# Multiplex_Registers.net
KiCad netlist of a schematic drawn in Altium Designer
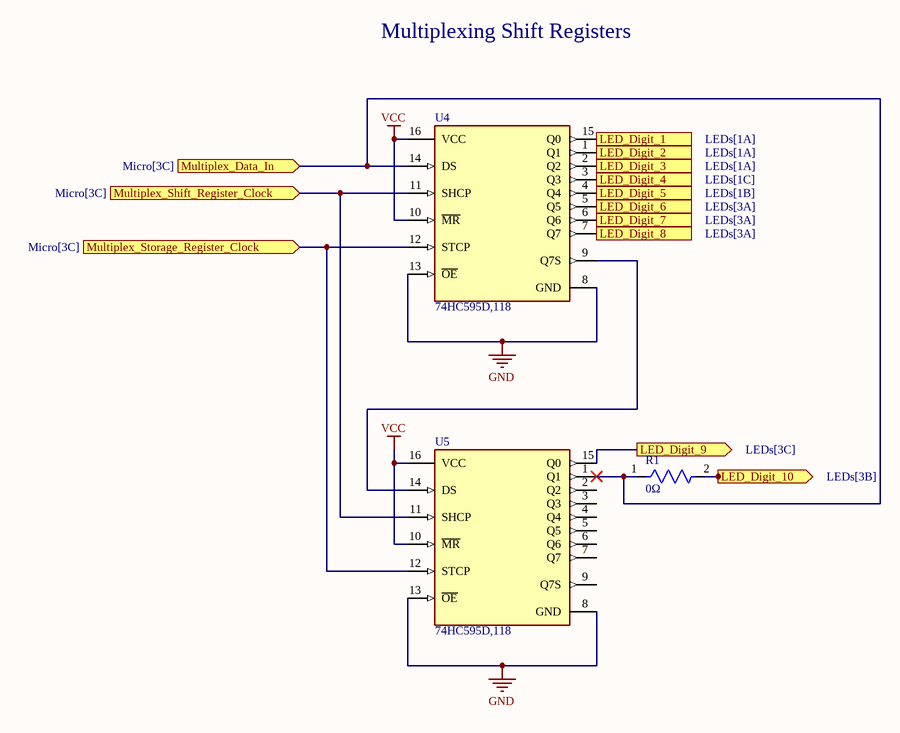
[diagram p0: Multiplex_Registers.SchDoc]

(export (version "E")
  (design (tool "Eeschema 10.0.6"))
  (components
    (comp (ref "R1")
      (value "CRCW04020000Z0ED")
      (footprint "FP-CRCW0402-e3-IPC_C")
      (description "RES Thick Film, 0Ω, 0.063W, 0402")
      (fields (field (name "TOLERANCE") "5%"))
      (libsource (lib "Altium Content Vault") (part "1029c3af85768c4190bb7ad29bc67b5"))
    )
    (comp (ref "U4")
      (value "74HC595D,118")
      (footprint "FP-SOT109-1-IPC_C")
      (description "IC SHIFT REGISTER 8BIT 16SOIC")
      (libsource (lib "Altium Content Vault") (part "7b153f231cfcc3ac06dee253bd56617"))
    )
    (comp (ref "U5")
      (value "74HC595D,118")
      (footprint "FP-SOT109-1-IPC_C")
      (description "IC SHIFT REGISTER 8BIT 16SOIC")
      (libsource (lib "Altium Content Vault") (part "7b153f231cfcc3ac06dee253bd56617"))
    )
  )
  (nets
    (net (code "1") (name "/LED_Digit_1") (class "Default")
      (node (ref "U4") (pin "15") (pinfunction "Q0_15") (pintype "output"))
    )
    (net (code "2") (name "/LED_Digit_2") (class "Default")
      (node (ref "U4") (pin "1") (pinfunction "Q1_1") (pintype "output"))
    )
    (net (code "3") (name "/LED_Digit_3") (class "Default")
      (node (ref "U4") (pin "2") (pinfunction "Q2_2") (pintype "output"))
    )
    (net (code "4") (name "/LED_Digit_4") (class "Default")
      (node (ref "U4") (pin "3") (pinfunction "Q3_3") (pintype "output"))
    )
    (net (code "5") (name "/LED_Digit_5") (class "Default")
      (node (ref "U4") (pin "4") (pinfunction "Q4_4") (pintype "output"))
    )
    (net (code "6") (name "/LED_Digit_6") (class "Default")
      (node (ref "U4") (pin "5") (pinfunction "Q5_5") (pintype "output"))
    )
    (net (code "7") (name "/LED_Digit_7") (class "Default")
      (node (ref "U4") (pin "6") (pinfunction "Q6_6") (pintype "output"))
    )
    (net (code "8") (name "/LED_Digit_8") (class "Default")
      (node (ref "U4") (pin "7") (pinfunction "Q7_7") (pintype "output"))
    )
    (net (code "9") (name "/LED_Digit_9") (class "Default")
      (node (ref "U5") (pin "15") (pinfunction "Q0_15") (pintype "output"))
    )
    (net (code "10") (name "/LED_Digit_10") (class "Default")
      (node (ref "R1") (pin "2") (pinfunction "2_2") (pintype "passive"))
    )
    (net (code "11") (name "/Multiplex_Data_In") (class "Default")
      (node (ref "R1") (pin "1") (pinfunction "1_1") (pintype "passive"))
      (node (ref "U4") (pin "14") (pinfunction "DS_14") (pintype "input"))
      (node (ref "U5") (pin "1") (pinfunction "Q1_1") (pintype "output"))
    )
    (net (code "12") (name "/Multiplex_Shift_Register_Clock") (class "Default")
      (node (ref "U4") (pin "11") (pinfunction "SHCP_11") (pintype "input"))
      (node (ref "U5") (pin "11") (pinfunction "SHCP_11") (pintype "input"))
    )
    (net (code "13") (name "/Multiplex_Storage_Register_Clock") (class "Default")
      (node (ref "U4") (pin "12") (pinfunction "STCP_12") (pintype "input"))
      (node (ref "U5") (pin "12") (pinfunction "STCP_12") (pintype "input"))
    )
    (net (code "14") (name "GND") (class "Default")
      (node (ref "U4") (pin "13") (pinfunction "~{OE}_13") (pintype "input"))
      (node (ref "U4") (pin "8") (pinfunction "GND_8") (pintype "power_in"))
      (node (ref "U5") (pin "13") (pinfunction "~{OE}_13") (pintype "input"))
      (node (ref "U5") (pin "8") (pinfunction "GND_8") (pintype "power_in"))
    )
    (net (code "15") (name "Net-(U4-Q7S)") (class "Default")
      (node (ref "U4") (pin "9") (pinfunction "Q7S_9") (pintype "output"))
      (node (ref "U5") (pin "14") (pinfunction "DS_14") (pintype "input"))
    )
    (net (code "16") (name "VCC") (class "Default")
      (node (ref "U4") (pin "10") (pinfunction "~{MR}_10") (pintype "input"))
      (node (ref "U4") (pin "16") (pinfunction "VCC_16") (pintype "power_in"))
      (node (ref "U5") (pin "10") (pinfunction "~{MR}_10") (pintype "input"))
      (node (ref "U5") (pin "16") (pinfunction "VCC_16") (pintype "power_in"))
    )
    (net (code "17") (name "unconnected-(U5-Q2-Pad2)") (class "Default")
      (node (ref "U5") (pin "2") (pinfunction "Q2_2") (pintype "output"))
    )
    (net (code "18") (name "unconnected-(U5-Q3-Pad3)") (class "Default")
      (node (ref "U5") (pin "3") (pinfunction "Q3_3") (pintype "output"))
    )
    (net (code "19") (name "unconnected-(U5-Q4-Pad4)") (class "Default")
      (node (ref "U5") (pin "4") (pinfunction "Q4_4") (pintype "output"))
    )
    (net (code "20") (name "unconnected-(U5-Q5-Pad5)") (class "Default")
      (node (ref "U5") (pin "5") (pinfunction "Q5_5") (pintype "output"))
    )
    (net (code "21") (name "unconnected-(U5-Q6-Pad6)") (class "Default")
      (node (ref "U5") (pin "6") (pinfunction "Q6_6") (pintype "output"))
    )
    (net (code "22") (name "unconnected-(U5-Q7-Pad7)") (class "Default")
      (node (ref "U5") (pin "7") (pinfunction "Q7_7") (pintype "output"))
    )
    (net (code "23") (name "unconnected-(U5-Q7S-Pad9)") (class "Default")
      (node (ref "U5") (pin "9") (pinfunction "Q7S_9") (pintype "output"))
    )
  )
)
